# DenScript_5x5_Strip_Board.net
KiCad netlist of a schematic drawn in EAGLE
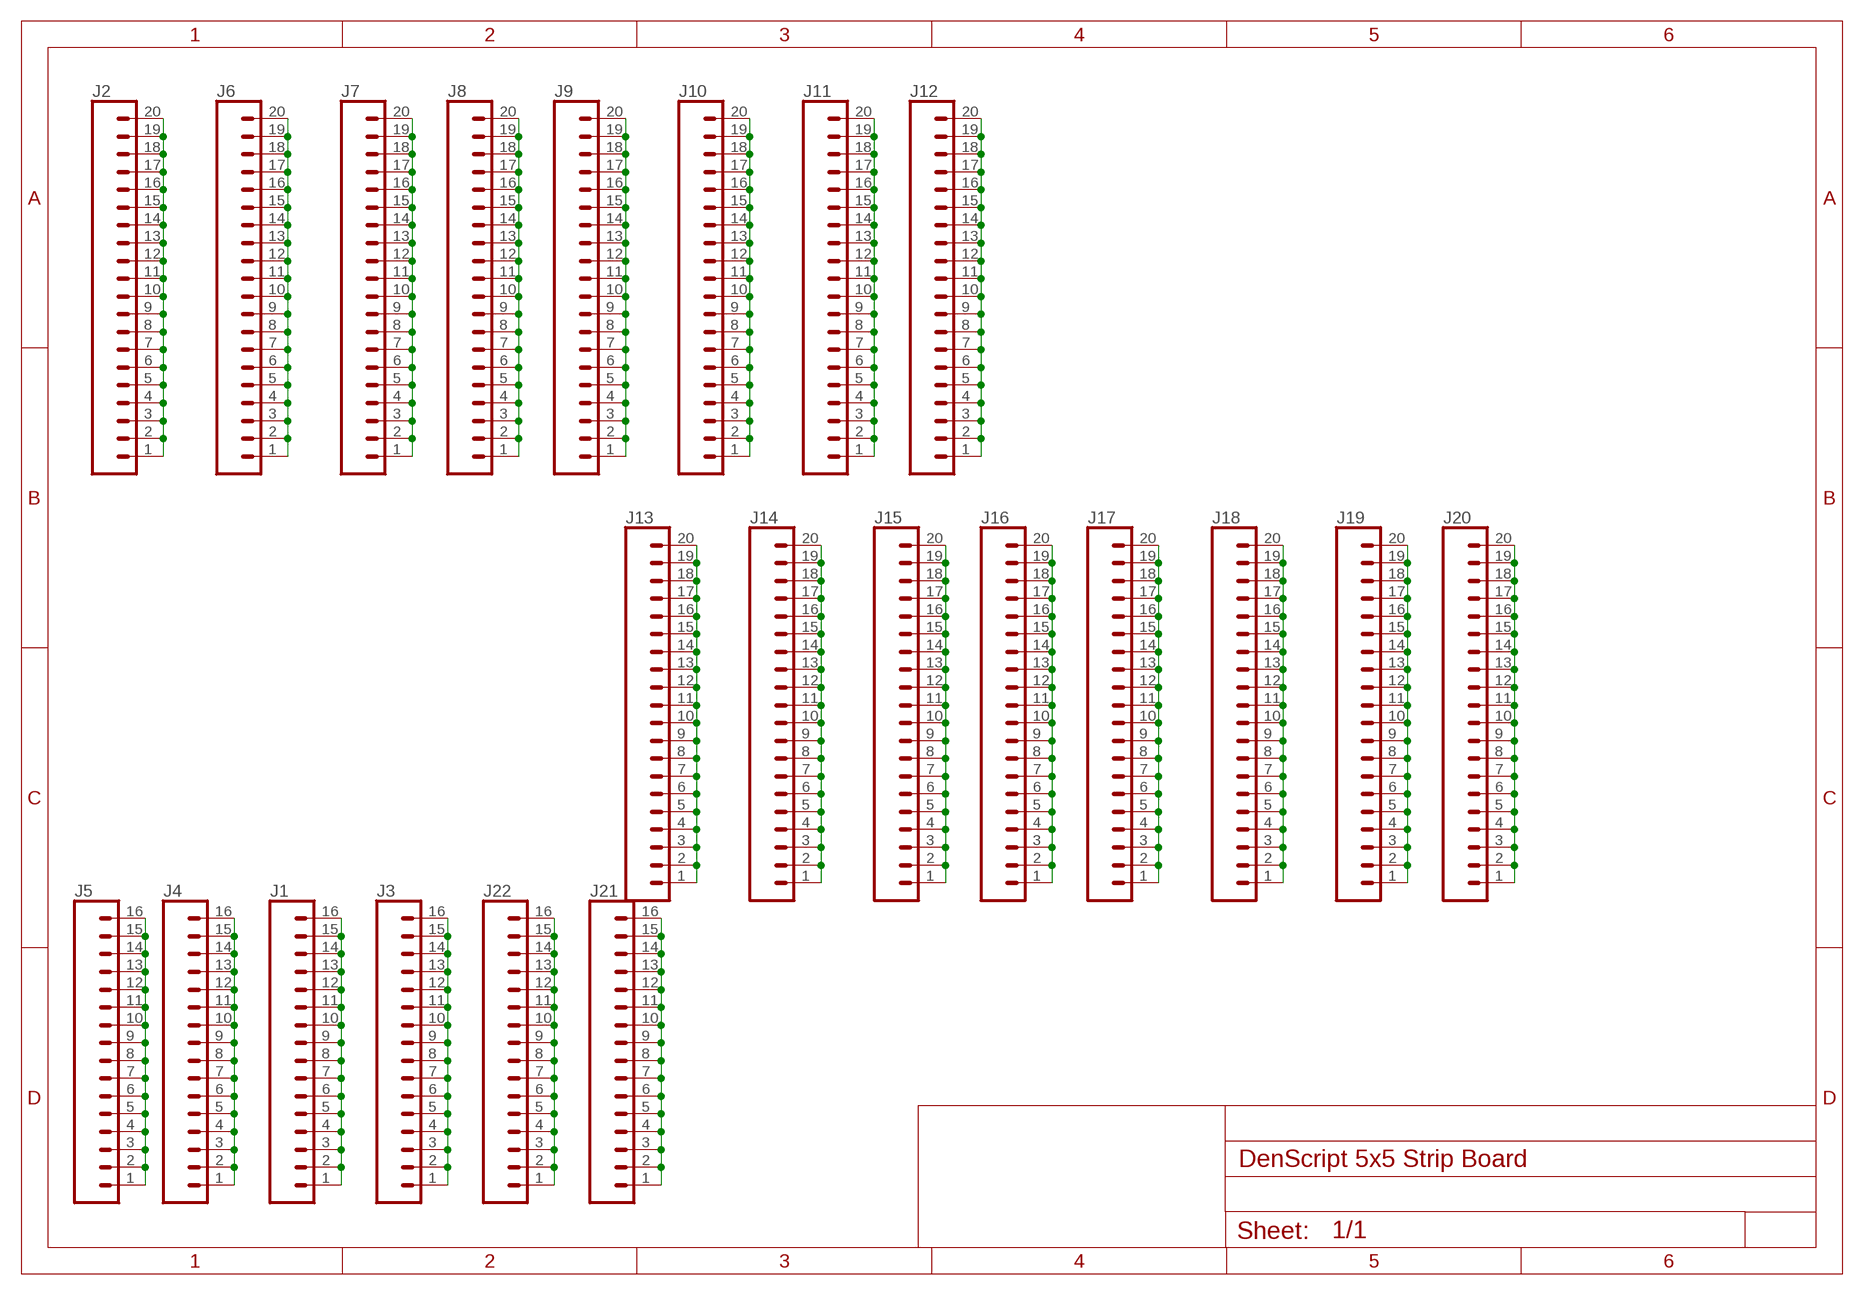
[diagram p0: schematic, sheet 1]

(export (version "E")
  (design (tool "Eeschema 10.0.6"))
  (components
    (comp (ref "J1")
      (value "CONN_161X16_NO_SILK")
      (footprint "eagle-import:1X16_NO_SILK")
      (libsource (lib "eagle-import") (part "CONN_161X16_NO_SILK"))
    )
    (comp (ref "J2")
      (value "CONN_20NOSILK")
      (footprint "eagle-import:1X20_NOSILK")
      (libsource (lib "eagle-import") (part "CONN_20NOSILK"))
    )
    (comp (ref "J3")
      (value "CONN_161X16_NO_SILK")
      (footprint "eagle-import:1X16_NO_SILK")
      (libsource (lib "eagle-import") (part "CONN_161X16_NO_SILK"))
    )
    (comp (ref "J4")
      (value "CONN_161X16_NO_SILK")
      (footprint "eagle-import:1X16_NO_SILK")
      (libsource (lib "eagle-import") (part "CONN_161X16_NO_SILK"))
    )
    (comp (ref "J5")
      (value "CONN_161X16_NO_SILK")
      (footprint "eagle-import:1X16_NO_SILK")
      (libsource (lib "eagle-import") (part "CONN_161X16_NO_SILK"))
    )
    (comp (ref "J6")
      (value "CONN_20NOSILK")
      (footprint "eagle-import:1X20_NOSILK")
      (libsource (lib "eagle-import") (part "CONN_20NOSILK"))
    )
    (comp (ref "J7")
      (value "CONN_20NOSILK")
      (footprint "eagle-import:1X20_NOSILK")
      (libsource (lib "eagle-import") (part "CONN_20NOSILK"))
    )
    (comp (ref "J8")
      (value "CONN_20NOSILK")
      (footprint "eagle-import:1X20_NOSILK")
      (libsource (lib "eagle-import") (part "CONN_20NOSILK"))
    )
    (comp (ref "J9")
      (value "CONN_20NOSILK")
      (footprint "eagle-import:1X20_NOSILK")
      (libsource (lib "eagle-import") (part "CONN_20NOSILK"))
    )
    (comp (ref "J10")
      (value "CONN_20NOSILK")
      (footprint "eagle-import:1X20_NOSILK")
      (libsource (lib "eagle-import") (part "CONN_20NOSILK"))
    )
    (comp (ref "J11")
      (value "CONN_20NOSILK")
      (footprint "eagle-import:1X20_NOSILK")
      (libsource (lib "eagle-import") (part "CONN_20NOSILK"))
    )
    (comp (ref "J12")
      (value "CONN_20NOSILK")
      (footprint "eagle-import:1X20_NOSILK")
      (libsource (lib "eagle-import") (part "CONN_20NOSILK"))
    )
    (comp (ref "J13")
      (value "CONN_20NOSILK")
      (footprint "eagle-import:1X20_NOSILK")
      (libsource (lib "eagle-import") (part "CONN_20NOSILK"))
    )
    (comp (ref "J14")
      (value "CONN_20NOSILK")
      (footprint "eagle-import:1X20_NOSILK")
      (libsource (lib "eagle-import") (part "CONN_20NOSILK"))
    )
    (comp (ref "J15")
      (value "CONN_20NOSILK")
      (footprint "eagle-import:1X20_NOSILK")
      (libsource (lib "eagle-import") (part "CONN_20NOSILK"))
    )
    (comp (ref "J16")
      (value "CONN_20NOSILK")
      (footprint "eagle-import:1X20_NOSILK")
      (libsource (lib "eagle-import") (part "CONN_20NOSILK"))
    )
    (comp (ref "J17")
      (value "CONN_20NOSILK")
      (footprint "eagle-import:1X20_NOSILK")
      (libsource (lib "eagle-import") (part "CONN_20NOSILK"))
    )
    (comp (ref "J18")
      (value "CONN_20NOSILK")
      (footprint "eagle-import:1X20_NOSILK")
      (libsource (lib "eagle-import") (part "CONN_20NOSILK"))
    )
    (comp (ref "J19")
      (value "CONN_20NOSILK")
      (footprint "eagle-import:1X20_NOSILK")
      (libsource (lib "eagle-import") (part "CONN_20NOSILK"))
    )
    (comp (ref "J20")
      (value "CONN_20NOSILK")
      (footprint "eagle-import:1X20_NOSILK")
      (libsource (lib "eagle-import") (part "CONN_20NOSILK"))
    )
    (comp (ref "J21")
      (value "CONN_161X16_NO_SILK")
      (footprint "eagle-import:1X16_NO_SILK")
      (libsource (lib "eagle-import") (part "CONN_161X16_NO_SILK"))
    )
    (comp (ref "J22")
      (value "CONN_161X16_NO_SILK")
      (footprint "eagle-import:1X16_NO_SILK")
      (libsource (lib "eagle-import") (part "CONN_161X16_NO_SILK"))
    )
  )
  (nets
    (net (code "1") (name "Net-(J1-Pad1)") (class "Default")
      (node (ref "J1") (pin "1") (pinfunction "1_1") (pintype "passive"))
      (node (ref "J1") (pin "10") (pinfunction "10_10") (pintype "passive"))
      (node (ref "J1") (pin "11") (pinfunction "11_11") (pintype "passive"))
      (node (ref "J1") (pin "12") (pinfunction "12_12") (pintype "passive"))
      (node (ref "J1") (pin "13") (pinfunction "13_13") (pintype "passive"))
      (node (ref "J1") (pin "14") (pinfunction "14_14") (pintype "passive"))
      (node (ref "J1") (pin "15") (pinfunction "15_15") (pintype "passive"))
      (node (ref "J1") (pin "16") (pinfunction "16_16") (pintype "passive"))
      (node (ref "J1") (pin "2") (pinfunction "2_2") (pintype "passive"))
      (node (ref "J1") (pin "3") (pinfunction "3_3") (pintype "passive"))
      (node (ref "J1") (pin "4") (pinfunction "4_4") (pintype "passive"))
      (node (ref "J1") (pin "5") (pinfunction "5_5") (pintype "passive"))
      (node (ref "J1") (pin "6") (pinfunction "6_6") (pintype "passive"))
      (node (ref "J1") (pin "7") (pinfunction "7_7") (pintype "passive"))
      (node (ref "J1") (pin "8") (pinfunction "8_8") (pintype "passive"))
      (node (ref "J1") (pin "9") (pinfunction "9_9") (pintype "passive"))
    )
    (net (code "2") (name "Net-(J2-Pad1)") (class "Default")
      (node (ref "J2") (pin "1") (pinfunction "1_1") (pintype "passive"))
      (node (ref "J2") (pin "10") (pinfunction "10_10") (pintype "passive"))
      (node (ref "J2") (pin "11") (pinfunction "11_11") (pintype "passive"))
      (node (ref "J2") (pin "12") (pinfunction "12_12") (pintype "passive"))
      (node (ref "J2") (pin "13") (pinfunction "13_13") (pintype "passive"))
      (node (ref "J2") (pin "14") (pinfunction "14_14") (pintype "passive"))
      (node (ref "J2") (pin "15") (pinfunction "15_15") (pintype "passive"))
      (node (ref "J2") (pin "16") (pinfunction "16_16") (pintype "passive"))
      (node (ref "J2") (pin "17") (pinfunction "17_17") (pintype "passive"))
      (node (ref "J2") (pin "18") (pinfunction "18_18") (pintype "passive"))
      (node (ref "J2") (pin "19") (pinfunction "19_19") (pintype "passive"))
      (node (ref "J2") (pin "2") (pinfunction "2_2") (pintype "passive"))
      (node (ref "J2") (pin "20") (pinfunction "20_20") (pintype "passive"))
      (node (ref "J2") (pin "3") (pinfunction "3_3") (pintype "passive"))
      (node (ref "J2") (pin "4") (pinfunction "4_4") (pintype "passive"))
      (node (ref "J2") (pin "5") (pinfunction "5_5") (pintype "passive"))
      (node (ref "J2") (pin "6") (pinfunction "6_6") (pintype "passive"))
      (node (ref "J2") (pin "7") (pinfunction "7_7") (pintype "passive"))
      (node (ref "J2") (pin "8") (pinfunction "8_8") (pintype "passive"))
      (node (ref "J2") (pin "9") (pinfunction "9_9") (pintype "passive"))
    )
    (net (code "3") (name "Net-(J3-Pad1)") (class "Default")
      (node (ref "J3") (pin "1") (pinfunction "1_1") (pintype "passive"))
      (node (ref "J3") (pin "10") (pinfunction "10_10") (pintype "passive"))
      (node (ref "J3") (pin "11") (pinfunction "11_11") (pintype "passive"))
      (node (ref "J3") (pin "12") (pinfunction "12_12") (pintype "passive"))
      (node (ref "J3") (pin "13") (pinfunction "13_13") (pintype "passive"))
      (node (ref "J3") (pin "14") (pinfunction "14_14") (pintype "passive"))
      (node (ref "J3") (pin "15") (pinfunction "15_15") (pintype "passive"))
      (node (ref "J3") (pin "16") (pinfunction "16_16") (pintype "passive"))
      (node (ref "J3") (pin "2") (pinfunction "2_2") (pintype "passive"))
      (node (ref "J3") (pin "3") (pinfunction "3_3") (pintype "passive"))
      (node (ref "J3") (pin "4") (pinfunction "4_4") (pintype "passive"))
      (node (ref "J3") (pin "5") (pinfunction "5_5") (pintype "passive"))
      (node (ref "J3") (pin "6") (pinfunction "6_6") (pintype "passive"))
      (node (ref "J3") (pin "7") (pinfunction "7_7") (pintype "passive"))
      (node (ref "J3") (pin "8") (pinfunction "8_8") (pintype "passive"))
      (node (ref "J3") (pin "9") (pinfunction "9_9") (pintype "passive"))
    )
    (net (code "4") (name "Net-(J4-Pad1)") (class "Default")
      (node (ref "J4") (pin "1") (pinfunction "1_1") (pintype "passive"))
      (node (ref "J4") (pin "10") (pinfunction "10_10") (pintype "passive"))
      (node (ref "J4") (pin "11") (pinfunction "11_11") (pintype "passive"))
      (node (ref "J4") (pin "12") (pinfunction "12_12") (pintype "passive"))
      (node (ref "J4") (pin "13") (pinfunction "13_13") (pintype "passive"))
      (node (ref "J4") (pin "14") (pinfunction "14_14") (pintype "passive"))
      (node (ref "J4") (pin "15") (pinfunction "15_15") (pintype "passive"))
      (node (ref "J4") (pin "16") (pinfunction "16_16") (pintype "passive"))
      (node (ref "J4") (pin "2") (pinfunction "2_2") (pintype "passive"))
      (node (ref "J4") (pin "3") (pinfunction "3_3") (pintype "passive"))
      (node (ref "J4") (pin "4") (pinfunction "4_4") (pintype "passive"))
      (node (ref "J4") (pin "5") (pinfunction "5_5") (pintype "passive"))
      (node (ref "J4") (pin "6") (pinfunction "6_6") (pintype "passive"))
      (node (ref "J4") (pin "7") (pinfunction "7_7") (pintype "passive"))
      (node (ref "J4") (pin "8") (pinfunction "8_8") (pintype "passive"))
      (node (ref "J4") (pin "9") (pinfunction "9_9") (pintype "passive"))
    )
    (net (code "5") (name "Net-(J5-Pad1)") (class "Default")
      (node (ref "J5") (pin "1") (pinfunction "1_1") (pintype "passive"))
      (node (ref "J5") (pin "10") (pinfunction "10_10") (pintype "passive"))
      (node (ref "J5") (pin "11") (pinfunction "11_11") (pintype "passive"))
      (node (ref "J5") (pin "12") (pinfunction "12_12") (pintype "passive"))
      (node (ref "J5") (pin "13") (pinfunction "13_13") (pintype "passive"))
      (node (ref "J5") (pin "14") (pinfunction "14_14") (pintype "passive"))
      (node (ref "J5") (pin "15") (pinfunction "15_15") (pintype "passive"))
      (node (ref "J5") (pin "16") (pinfunction "16_16") (pintype "passive"))
      (node (ref "J5") (pin "2") (pinfunction "2_2") (pintype "passive"))
      (node (ref "J5") (pin "3") (pinfunction "3_3") (pintype "passive"))
      (node (ref "J5") (pin "4") (pinfunction "4_4") (pintype "passive"))
      (node (ref "J5") (pin "5") (pinfunction "5_5") (pintype "passive"))
      (node (ref "J5") (pin "6") (pinfunction "6_6") (pintype "passive"))
      (node (ref "J5") (pin "7") (pinfunction "7_7") (pintype "passive"))
      (node (ref "J5") (pin "8") (pinfunction "8_8") (pintype "passive"))
      (node (ref "J5") (pin "9") (pinfunction "9_9") (pintype "passive"))
    )
    (net (code "6") (name "Net-(J6-Pad1)") (class "Default")
      (node (ref "J6") (pin "1") (pinfunction "1_1") (pintype "passive"))
      (node (ref "J6") (pin "10") (pinfunction "10_10") (pintype "passive"))
      (node (ref "J6") (pin "11") (pinfunction "11_11") (pintype "passive"))
      (node (ref "J6") (pin "12") (pinfunction "12_12") (pintype "passive"))
      (node (ref "J6") (pin "13") (pinfunction "13_13") (pintype "passive"))
      (node (ref "J6") (pin "14") (pinfunction "14_14") (pintype "passive"))
      (node (ref "J6") (pin "15") (pinfunction "15_15") (pintype "passive"))
      (node (ref "J6") (pin "16") (pinfunction "16_16") (pintype "passive"))
      (node (ref "J6") (pin "17") (pinfunction "17_17") (pintype "passive"))
      (node (ref "J6") (pin "18") (pinfunction "18_18") (pintype "passive"))
      (node (ref "J6") (pin "19") (pinfunction "19_19") (pintype "passive"))
      (node (ref "J6") (pin "2") (pinfunction "2_2") (pintype "passive"))
      (node (ref "J6") (pin "20") (pinfunction "20_20") (pintype "passive"))
      (node (ref "J6") (pin "3") (pinfunction "3_3") (pintype "passive"))
      (node (ref "J6") (pin "4") (pinfunction "4_4") (pintype "passive"))
      (node (ref "J6") (pin "5") (pinfunction "5_5") (pintype "passive"))
      (node (ref "J6") (pin "6") (pinfunction "6_6") (pintype "passive"))
      (node (ref "J6") (pin "7") (pinfunction "7_7") (pintype "passive"))
      (node (ref "J6") (pin "8") (pinfunction "8_8") (pintype "passive"))
      (node (ref "J6") (pin "9") (pinfunction "9_9") (pintype "passive"))
    )
    (net (code "7") (name "Net-(J7-Pad1)") (class "Default")
      (node (ref "J7") (pin "1") (pinfunction "1_1") (pintype "passive"))
      (node (ref "J7") (pin "10") (pinfunction "10_10") (pintype "passive"))
      (node (ref "J7") (pin "11") (pinfunction "11_11") (pintype "passive"))
      (node (ref "J7") (pin "12") (pinfunction "12_12") (pintype "passive"))
      (node (ref "J7") (pin "13") (pinfunction "13_13") (pintype "passive"))
      (node (ref "J7") (pin "14") (pinfunction "14_14") (pintype "passive"))
      (node (ref "J7") (pin "15") (pinfunction "15_15") (pintype "passive"))
      (node (ref "J7") (pin "16") (pinfunction "16_16") (pintype "passive"))
      (node (ref "J7") (pin "17") (pinfunction "17_17") (pintype "passive"))
      (node (ref "J7") (pin "18") (pinfunction "18_18") (pintype "passive"))
      (node (ref "J7") (pin "19") (pinfunction "19_19") (pintype "passive"))
      (node (ref "J7") (pin "2") (pinfunction "2_2") (pintype "passive"))
      (node (ref "J7") (pin "20") (pinfunction "20_20") (pintype "passive"))
      (node (ref "J7") (pin "3") (pinfunction "3_3") (pintype "passive"))
      (node (ref "J7") (pin "4") (pinfunction "4_4") (pintype "passive"))
      (node (ref "J7") (pin "5") (pinfunction "5_5") (pintype "passive"))
      (node (ref "J7") (pin "6") (pinfunction "6_6") (pintype "passive"))
      (node (ref "J7") (pin "7") (pinfunction "7_7") (pintype "passive"))
      (node (ref "J7") (pin "8") (pinfunction "8_8") (pintype "passive"))
      (node (ref "J7") (pin "9") (pinfunction "9_9") (pintype "passive"))
    )
    (net (code "8") (name "Net-(J8-Pad1)") (class "Default")
      (node (ref "J8") (pin "1") (pinfunction "1_1") (pintype "passive"))
      (node (ref "J8") (pin "10") (pinfunction "10_10") (pintype "passive"))
      (node (ref "J8") (pin "11") (pinfunction "11_11") (pintype "passive"))
      (node (ref "J8") (pin "12") (pinfunction "12_12") (pintype "passive"))
      (node (ref "J8") (pin "13") (pinfunction "13_13") (pintype "passive"))
      (node (ref "J8") (pin "14") (pinfunction "14_14") (pintype "passive"))
      (node (ref "J8") (pin "15") (pinfunction "15_15") (pintype "passive"))
      (node (ref "J8") (pin "16") (pinfunction "16_16") (pintype "passive"))
      (node (ref "J8") (pin "17") (pinfunction "17_17") (pintype "passive"))
      (node (ref "J8") (pin "18") (pinfunction "18_18") (pintype "passive"))
      (node (ref "J8") (pin "19") (pinfunction "19_19") (pintype "passive"))
      (node (ref "J8") (pin "2") (pinfunction "2_2") (pintype "passive"))
      (node (ref "J8") (pin "20") (pinfunction "20_20") (pintype "passive"))
      (node (ref "J8") (pin "3") (pinfunction "3_3") (pintype "passive"))
      (node (ref "J8") (pin "4") (pinfunction "4_4") (pintype "passive"))
      (node (ref "J8") (pin "5") (pinfunction "5_5") (pintype "passive"))
      (node (ref "J8") (pin "6") (pinfunction "6_6") (pintype "passive"))
      (node (ref "J8") (pin "7") (pinfunction "7_7") (pintype "passive"))
      (node (ref "J8") (pin "8") (pinfunction "8_8") (pintype "passive"))
      (node (ref "J8") (pin "9") (pinfunction "9_9") (pintype "passive"))
    )
    (net (code "9") (name "Net-(J9-Pad1)") (class "Default")
      (node (ref "J9") (pin "1") (pinfunction "1_1") (pintype "passive"))
      (node (ref "J9") (pin "10") (pinfunction "10_10") (pintype "passive"))
      (node (ref "J9") (pin "11") (pinfunction "11_11") (pintype "passive"))
      (node (ref "J9") (pin "12") (pinfunction "12_12") (pintype "passive"))
      (node (ref "J9") (pin "13") (pinfunction "13_13") (pintype "passive"))
      (node (ref "J9") (pin "14") (pinfunction "14_14") (pintype "passive"))
      (node (ref "J9") (pin "15") (pinfunction "15_15") (pintype "passive"))
      (node (ref "J9") (pin "16") (pinfunction "16_16") (pintype "passive"))
      (node (ref "J9") (pin "17") (pinfunction "17_17") (pintype "passive"))
      (node (ref "J9") (pin "18") (pinfunction "18_18") (pintype "passive"))
      (node (ref "J9") (pin "19") (pinfunction "19_19") (pintype "passive"))
      (node (ref "J9") (pin "2") (pinfunction "2_2") (pintype "passive"))
      (node (ref "J9") (pin "20") (pinfunction "20_20") (pintype "passive"))
      (node (ref "J9") (pin "3") (pinfunction "3_3") (pintype "passive"))
      (node (ref "J9") (pin "4") (pinfunction "4_4") (pintype "passive"))
      (node (ref "J9") (pin "5") (pinfunction "5_5") (pintype "passive"))
      (node (ref "J9") (pin "6") (pinfunction "6_6") (pintype "passive"))
      (node (ref "J9") (pin "7") (pinfunction "7_7") (pintype "passive"))
      (node (ref "J9") (pin "8") (pinfunction "8_8") (pintype "passive"))
      (node (ref "J9") (pin "9") (pinfunction "9_9") (pintype "passive"))
    )
    (net (code "10") (name "Net-(J10-Pad1)") (class "Default")
      (node (ref "J10") (pin "1") (pinfunction "1_1") (pintype "passive"))
      (node (ref "J10") (pin "10") (pinfunction "10_10") (pintype "passive"))
      (node (ref "J10") (pin "11") (pinfunction "11_11") (pintype "passive"))
      (node (ref "J10") (pin "12") (pinfunction "12_12") (pintype "passive"))
      (node (ref "J10") (pin "13") (pinfunction "13_13") (pintype "passive"))
      (node (ref "J10") (pin "14") (pinfunction "14_14") (pintype "passive"))
      (node (ref "J10") (pin "15") (pinfunction "15_15") (pintype "passive"))
      (node (ref "J10") (pin "16") (pinfunction "16_16") (pintype "passive"))
      (node (ref "J10") (pin "17") (pinfunction "17_17") (pintype "passive"))
      (node (ref "J10") (pin "18") (pinfunction "18_18") (pintype "passive"))
      (node (ref "J10") (pin "19") (pinfunction "19_19") (pintype "passive"))
      (node (ref "J10") (pin "2") (pinfunction "2_2") (pintype "passive"))
      (node (ref "J10") (pin "20") (pinfunction "20_20") (pintype "passive"))
      (node (ref "J10") (pin "3") (pinfunction "3_3") (pintype "passive"))
      (node (ref "J10") (pin "4") (pinfunction "4_4") (pintype "passive"))
      (node (ref "J10") (pin "5") (pinfunction "5_5") (pintype "passive"))
      (node (ref "J10") (pin "6") (pinfunction "6_6") (pintype "passive"))
      (node (ref "J10") (pin "7") (pinfunction "7_7") (pintype "passive"))
      (node (ref "J10") (pin "8") (pinfunction "8_8") (pintype "passive"))
      (node (ref "J10") (pin "9") (pinfunction "9_9") (pintype "passive"))
    )
    (net (code "11") (name "Net-(J11-Pad1)") (class "Default")
      (node (ref "J11") (pin "1") (pinfunction "1_1") (pintype "passive"))
      (node (ref "J11") (pin "10") (pinfunction "10_10") (pintype "passive"))
      (node (ref "J11") (pin "11") (pinfunction "11_11") (pintype "passive"))
      (node (ref "J11") (pin "12") (pinfunction "12_12") (pintype "passive"))
      (node (ref "J11") (pin "13") (pinfunction "13_13") (pintype "passive"))
      (node (ref "J11") (pin "14") (pinfunction "14_14") (pintype "passive"))
      (node (ref "J11") (pin "15") (pinfunction "15_15") (pintype "passive"))
      (node (ref "J11") (pin "16") (pinfunction "16_16") (pintype "passive"))
      (node (ref "J11") (pin "17") (pinfunction "17_17") (pintype "passive"))
      (node (ref "J11") (pin "18") (pinfunction "18_18") (pintype "passive"))
      (node (ref "J11") (pin "19") (pinfunction "19_19") (pintype "passive"))
      (node (ref "J11") (pin "2") (pinfunction "2_2") (pintype "passive"))
      (node (ref "J11") (pin "20") (pinfunction "20_20") (pintype "passive"))
      (node (ref "J11") (pin "3") (pinfunction "3_3") (pintype "passive"))
      (node (ref "J11") (pin "4") (pinfunction "4_4") (pintype "passive"))
      (node (ref "J11") (pin "5") (pinfunction "5_5") (pintype "passive"))
      (node (ref "J11") (pin "6") (pinfunction "6_6") (pintype "passive"))
      (node (ref "J11") (pin "7") (pinfunction "7_7") (pintype "passive"))
      (node (ref "J11") (pin "8") (pinfunction "8_8") (pintype "passive"))
      (node (ref "J11") (pin "9") (pinfunction "9_9") (pintype "passive"))
    )
    (net (code "12") (name "Net-(J12-Pad1)") (class "Default")
      (node (ref "J12") (pin "1") (pinfunction "1_1") (pintype "passive"))
      (node (ref "J12") (pin "10") (pinfunction "10_10") (pintype "passive"))
      (node (ref "J12") (pin "11") (pinfunction "11_11") (pintype "passive"))
      (node (ref "J12") (pin "12") (pinfunction "12_12") (pintype "passive"))
      (node (ref "J12") (pin "13") (pinfunction "13_13") (pintype "passive"))
      (node (ref "J12") (pin "14") (pinfunction "14_14") (pintype "passive"))
      (node (ref "J12") (pin "15") (pinfunction "15_15") (pintype "passive"))
      (node (ref "J12") (pin "16") (pinfunction "16_16") (pintype "passive"))
      (node (ref "J12") (pin "17") (pinfunction "17_17") (pintype "passive"))
      (node (ref "J12") (pin "18") (pinfunction "18_18") (pintype "passive"))
      (node (ref "J12") (pin "19") (pinfunction "19_19") (pintype "passive"))
      (node (ref "J12") (pin "2") (pinfunction "2_2") (pintype "passive"))
      (node (ref "J12") (pin "20") (pinfunction "20_20") (pintype "passive"))
      (node (ref "J12") (pin "3") (pinfunction "3_3") (pintype "passive"))
      (node (ref "J12") (pin "4") (pinfunction "4_4") (pintype "passive"))
      (node (ref "J12") (pin "5") (pinfunction "5_5") (pintype "passive"))
      (node (ref "J12") (pin "6") (pinfunction "6_6") (pintype "passive"))
      (node (ref "J12") (pin "7") (pinfunction "7_7") (pintype "passive"))
      (node (ref "J12") (pin "8") (pinfunction "8_8") (pintype "passive"))
      (node (ref "J12") (pin "9") (pinfunction "9_9") (pintype "passive"))
    )
    (net (code "13") (name "Net-(J13-Pad1)") (class "Default")
      (node (ref "J13") (pin "1") (pinfunction "1_1") (pintype "passive"))
      (node (ref "J13") (pin "10") (pinfunction "10_10") (pintype "passive"))
      (node (ref "J13") (pin "11") (pinfunction "11_11") (pintype "passive"))
      (node (ref "J13") (pin "12") (pinfunction "12_12") (pintype "passive"))
      (node (ref "J13") (pin "13") (pinfunction "13_13") (pintype "passive"))
      (node (ref "J13") (pin "14") (pinfunction "14_14") (pintype "passive"))
      (node (ref "J13") (pin "15") (pinfunction "15_15") (pintype "passive"))
      (node (ref "J13") (pin "16") (pinfunction "16_16") (pintype "passive"))
      (node (ref "J13") (pin "17") (pinfunction "17_17") (pintype "passive"))
      (node (ref "J13") (pin "18") (pinfunction "18_18") (pintype "passive"))
      (node (ref "J13") (pin "19") (pinfunction "19_19") (pintype "passive"))
      (node (ref "J13") (pin "2") (pinfunction "2_2") (pintype "passive"))
      (node (ref "J13") (pin "20") (pinfunction "20_20") (pintype "passive"))
      (node (ref "J13") (pin "3") (pinfunction "3_3") (pintype "passive"))
      (node (ref "J13") (pin "4") (pinfunction "4_4") (pintype "passive"))
      (node (ref "J13") (pin "5") (pinfunction "5_5") (pintype "passive"))
      (node (ref "J13") (pin "6") (pinfunction "6_6") (pintype "passive"))
      (node (ref "J13") (pin "7") (pinfunction "7_7") (pintype "passive"))
      (node (ref "J13") (pin "8") (pinfunction "8_8") (pintype "passive"))
      (node (ref "J13") (pin "9") (pinfunction "9_9") (pintype "passive"))
    )
    (net (code "14") (name "Net-(J14-Pad1)") (class "Default")
      (node (ref "J14") (pin "1") (pinfunction "1_1") (pintype "passive"))
      (node (ref "J14") (pin "10") (pinfunction "10_10") (pintype "passive"))
      (node (ref "J14") (pin "11") (pinfunction "11_11") (pintype "passive"))
      (node (ref "J14") (pin "12") (pinfunction "12_12") (pintype "passive"))
      (node (ref "J14") (pin "13") (pinfunction "13_13") (pintype "passive"))
      (node (ref "J14") (pin "14") (pinfunction "14_14") (pintype "passive"))
      (node (ref "J14") (pin "15") (pinfunction "15_15") (pintype "passive"))
      (node (ref "J14") (pin "16") (pinfunction "16_16") (pintype "passive"))
      (node (ref "J14") (pin "17") (pinfunction "17_17") (pintype "passive"))
      (node (ref "J14") (pin "18") (pinfunction "18_18") (pintype "passive"))
      (node (ref "J14") (pin "19") (pinfunction "19_19") (pintype "passive"))
      (node (ref "J14") (pin "2") (pinfunction "2_2") (pintype "passive"))
      (node (ref "J14") (pin "20") (pinfunction "20_20") (pintype "passive"))
      (node (ref "J14") (pin "3") (pinfunction "3_3") (pintype "passive"))
      (node (ref "J14") (pin "4") (pinfunction "4_4") (pintype "passive"))
      (node (ref "J14") (pin "5") (pinfunction "5_5") (pintype "passive"))
      (node (ref "J14") (pin "6") (pinfunction "6_6") (pintype "passive"))
      (node (ref "J14") (pin "7") (pinfunction "7_7") (pintype "passive"))
      (node (ref "J14") (pin "8") (pinfunction "8_8") (pintype "passive"))
      (node (ref "J14") (pin "9") (pinfunction "9_9") (pintype "passive"))
    )
    (net (code "15") (name "Net-(J15-Pad1)") (class "Default")
      (node (ref "J15") (pin "1") (pinfunction "1_1") (pintype "passive"))
      (node (ref "J15") (pin "10") (pinfunction "10_10") (pintype "passive"))
      (node (ref "J15") (pin "11") (pinfunction "11_11") (pintype "passive"))
      (node (ref "J15") (pin "12") (pinfunction "12_12") (pintype "passive"))
      (node (ref "J15") (pin "13") (pinfunction "13_13") (pintype "passive"))
      (node (ref "J15") (pin "14") (pinfunction "14_14") (pintype "passive"))
      (node (ref "J15") (pin "15") (pinfunction "15_15") (pintype "passive"))
      (node (ref "J15") (pin "16") (pinfunction "16_16") (pintype "passive"))
      (node (ref "J15") (pin "17") (pinfunction "17_17") (pintype "passive"))
      (node (ref "J15") (pin "18") (pinfunction "18_18") (pintype "passive"))
      (node (ref "J15") (pin "19") (pinfunction "19_19") (pintype "passive"))
      (node (ref "J15") (pin "2") (pinfunction "2_2") (pintype "passive"))
      (node (ref "J15") (pin "20") (pinfunction "20_20") (pintype "passive"))
      (node (ref "J15") (pin "3") (pinfunction "3_3") (pintype "passive"))
      (node (ref "J15") (pin "4") (pinfunction "4_4") (pintype "passive"))
      (node (ref "J15") (pin "5") (pinfunction "5_5") (pintype "passive"))
      (node (ref "J15") (pin "6") (pinfunction "6_6") (pintype "passive"))
      (node (ref "J15") (pin "7") (pinfunction "7_7") (pintype "passive"))
      (node (ref "J15") (pin "8") (pinfunction "8_8") (pintype "passive"))
      (node (ref "J15") (pin "9") (pinfunction "9_9") (pintype "passive"))
    )
    (net (code "16") (name "Net-(J16-Pad1)") (class "Default")
      (node (ref "J16") (pin "1") (pinfunction "1_1") (pintype "passive"))
      (node (ref "J16") (pin "10") (pinfunction "10_10") (pintype "passive"))
      (node (ref "J16") (pin "11") (pinfunction "11_11") (pintype "passive"))
      (node (ref "J16") (pin "12") (pinfunction "12_12") (pintype "passive"))
      (node (ref "J16") (pin "13") (pinfunction "13_13") (pintype "passive"))
      (node (ref "J16") (pin "14") (pinfunction "14_14") (pintype "passive"))
      (node (ref "J16") (pin "15") (pinfunction "15_15") (pintype "passive"))
      (node (ref "J16") (pin "16") (pinfunction "16_16") (pintype "passive"))
      (node (ref "J16") (pin "17") (pinfunction "17_17") (pintype "passive"))
      (node (ref "J16") (pin "18") (pinfunction "18_18") (pintype "passive"))
      (node (ref "J16") (pin "19") (pinfunction "19_19") (pintype "passive"))
      (node (ref "J16") (pin "2") (pinfunction "2_2") (pintype "passive"))
      (node (ref "J16") (pin "20") (pinfunction "20_20") (pintype "passive"))
      (node (ref "J16") (pin "3") (pinfunction "3_3") (pintype "passive"))
      (node (ref "J16") (pin "4") (pinfunction "4_4") (pintype "passive"))
      (node (ref "J16") (pin "5") (pinfunction "5_5") (pintype "passive"))
      (node (ref "J16") (pin "6") (pinfunction "6_6") (pintype "passive"))
      (node (ref "J16") (pin "7") (pinfunction "7_7") (pintype "passive"))
      (node (ref "J16") (pin "8") (pinfunction "8_8") (pintype "passive"))
      (node (ref "J16") (pin "9") (pinfunction "9_9") (pintype "passive"))
    )
    (net (code "17") (name "Net-(J17-Pad1)") (class "Default")
      (node (ref "J17") (pin "1") (pinfunction "1_1") (pintype "passive"))
      (node (ref "J17") (pin "10") (pinfunction "10_10") (pintype "passive"))
      (node (ref "J17") (pin "11") (pinfunction "11_11") (pintype "passive"))
      (node (ref "J17") (pin "12") (pinfunction "12_12") (pintype "passive"))
      (node (ref "J17") (pin "13") (pinfunction "13_13") (pintype "passive"))
      (node (ref "J17") (pin "14") (pinfunction "14_14") (pintype "passive"))
      (node (ref "J17") (pin "15") (pinfunction "15_15") (pintype "passive"))
      (node (ref "J17") (pin "16") (pinfunction "16_16") (pintype "passive"))
      (node (ref "J17") (pin "17") (pinfunction "17_17") (pintype "passive"))
      (node (ref "J17") (pin "18") (pinfunction "18_18") (pintype "passive"))
      (node (ref "J17") (pin "19") (pinfunction "19_19") (pintype "passive"))
      (node (ref "J17") (pin "2") (pinfunction "2_2") (pintype "passive"))
      (node (ref "J17") (pin "20") (pinfunction "20_20") (pintype "passive"))
      (node (ref "J17") (pin "3") (pinfunction "3_3") (pintype "passive"))
      (node (ref "J17") (pin "4") (pinfunction "4_4") (pintype "passive"))
      (node (ref "J17") (pin "5") (pinfunction "5_5") (pintype "passive"))
      (node (ref "J17") (pin "6") (pinfunction "6_6") (pintype "passive"))
      (node (ref "J17") (pin "7") (pinfunction "7_7") (pintype "passive"))
      (node (ref "J17") (pin "8") (pinfunction "8_8") (pintype "passive"))
      (node (ref "J17") (pin "9") (pinfunction "9_9") (pintype "passive"))
    )
    (net (code "18") (name "Net-(J18-Pad1)") (class "Default")
      (node (ref "J18") (pin "1") (pinfunction "1_1") (pintype "passive"))
      (node (ref "J18") (pin "10") (pinfunction "10_10") (pintype "passive"))
      (node (ref "J18") (pin "11") (pinfunction "11_11") (pintype "passive"))
      (node (ref "J18") (pin "12") (pinfunction "12_12") (pintype "passive"))
      (node (ref "J18") (pin "13") (pinfunction "13_13") (pintype "passive"))
      (node (ref "J18") (pin "14") (pinfunction "14_14") (pintype "passive"))
      (node (ref "J18") (pin "15") (pinfunction "15_15") (pintype "passive"))
      (node (ref "J18") (pin "16") (pinfunction "16_16") (pintype "passive"))
      (node (ref "J18") (pin "17") (pinfunction "17_17") (pintype "passive"))
      (node (ref "J18") (pin "18") (pinfunction "18_18") (pintype "passive"))
      (node (ref "J18") (pin "19") (pinfunction "19_19") (pintype "passive"))
      (node (ref "J18") (pin "2") (pinfunction "2_2") (pintype "passive"))
      (node (ref "J18") (pin "20") (pinfunction "20_20") (pintype "passive"))
      (node (ref "J18") (pin "3") (pinfunction "3_3") (pintype "passive"))
      (node (ref "J18") (pin "4") (pinfunction "4_4") (pintype "passive"))
      (node (ref "J18") (pin "5") (pinfunction "5_5") (pintype "passive"))
      (node (ref "J18") (pin "6") (pinfunction "6_6") (pintype "passive"))
      (node (ref "J18") (pin "7") (pinfunction "7_7") (pintype "passive"))
      (node (ref "J18") (pin "8") (pinfunction "8_8") (pintype "passive"))
      (node (ref "J18") (pin "9") (pinfunction "9_9") (pintype "passive"))
    )
    (net (code "19") (name "Net-(J19-Pad1)") (class "Default")
      (node (ref "J19") (pin "1") (pinfunction "1_1") (pintype "passive"))
      (node (ref "J19") (pin "10") (pinfunction "10_10") (pintype "passive"))
      (node (ref "J19") (pin "11") (pinfunction "11_11") (pintype "passive"))
      (node (ref "J19") (pin "12") (pinfunction "12_12") (pintype "passive"))
      (node (ref "J19") (pin "13") (pinfunction "13_13") (pintype "passive"))
      (node (ref "J19") (pin "14") (pinfunction "14_14") (pintype "passive"))
      (node (ref "J19") (pin "15") (pinfunction "15_15") (pintype "passive"))
      (node (ref "J19") (pin "16") (pinfunction "16_16") (pintype "passive"))
      (node (ref "J19") (pin "17") (pinfunction "17_17") (pintype "passive"))
      (node (ref "J19") (pin "18") (pinfunction "18_18") (pintype "passive"))
      (node (ref "J19") (pin "19") (pinfunction "19_19") (pintype "passive"))
      (node (ref "J19") (pin "2") (pinfunction "2_2") (pintype "passive"))
      (node (ref "J19") (pin "20") (pinfunction "20_20") (pintype "passive"))
      (node (ref "J19") (pin "3") (pinfunction "3_3") (pintype "passive"))
      (node (ref "J19") (pin "4") (pinfunction "4_4") (pintype "passive"))
      (node (ref "J19") (pin "5") (pinfunction "5_5") (pintype "passive"))
      (node (ref "J19") (pin "6") (pinfunction "6_6") (pintype "passive"))
      (node (ref "J19") (pin "7") (pinfunction "7_7") (pintype "passive"))
      (node (ref "J19") (pin "8") (pinfunction "8_8") (pintype "passive"))
      (node (ref "J19") (pin "9") (pinfunction "9_9") (pintype "passive"))
    )
    (net (code "20") (name "Net-(J20-Pad1)") (class "Default")
      (node (ref "J20") (pin "1") (pinfunction "1_1") (pintype "passive"))
      (node (ref "J20") (pin "10") (pinfunction "10_10") (pintype "passive"))
      (node (ref "J20") (pin "11") (pinfunction "11_11") (pintype "passive"))
      (node (ref "J20") (pin "12") (pinfunction "12_12") (pintype "passive"))
      (node (ref "J20") (pin "13") (pinfunction "13_13") (pintype "passive"))
      (node (ref "J20") (pin "14") (pinfunction "14_14") (pintype "passive"))
      (node (ref "J20") (pin "15") (pinfunction "15_15") (pintype "passive"))
      (node (ref "J20") (pin "16") (pinfunction "16_16") (pintype "passive"))
      (node (ref "J20") (pin "17") (pinfunction "17_17") (pintype "passive"))
      (node (ref "J20") (pin "18") (pinfunction "18_18") (pintype "passive"))
      (node (ref "J20") (pin "19") (pinfunction "19_19") (pintype "passive"))
      (node (ref "J20") (pin "2") (pinfunction "2_2") (pintype "passive"))
      (node (ref "J20") (pin "20") (pinfunction "20_20") (pintype "passive"))
      (node (ref "J20") (pin "3") (pinfunction "3_3") (pintype "passive"))
      (node (ref "J20") (pin "4") (pinfunction "4_4") (pintype "passive"))
      (node (ref "J20") (pin "5") (pinfunction "5_5") (pintype "passive"))
      (node (ref "J20") (pin "6") (pinfunction "6_6") (pintype "passive"))
      (node (ref "J20") (pin "7") (pinfunction "7_7") (pintype "passive"))
      (node (ref "J20") (pin "8") (pinfunction "8_8") (pintype "passive"))
      (node (ref "J20") (pin "9") (pinfunction "9_9") (pintype "passive"))
    )
    (net (code "21") (name "Net-(J21-Pad1)") (class "Default")
      (node (ref "J21") (pin "1") (pinfunction "1_1") (pintype "passive"))
      (node (ref "J21") (pin "10") (pinfunction "10_10") (pintype "passive"))
      (node (ref "J21") (pin "11") (pinfunction "11_11") (pintype "passive"))
      (node (ref "J21") (pin "12") (pinfunction "12_12") (pintype "passive"))
      (node (ref "J21") (pin "13") (pinfunction "13_13") (pintype "passive"))
      (node (ref "J21") (pin "14") (pinfunction "14_14") (pintype "passive"))
      (node (ref "J21") (pin "15") (pinfunction "15_15") (pintype "passive"))
      (node (ref "J21") (pin "16") (pinfunction "16_16") (pintype "passive"))
      (node (ref "J21") (pin "2") (pinfunction "2_2") (pintype "passive"))
      (node (ref "J21") (pin "3") (pinfunction "3_3") (pintype "passive"))
      (node (ref "J21") (pin "4") (pinfunction "4_4") (pintype "passive"))
      (node (ref "J21") (pin "5") (pinfunction "5_5") (pintype "passive"))
      (node (ref "J21") (pin "6") (pinfunction "6_6") (pintype "passive"))
      (node (ref "J21") (pin "7") (pinfunction "7_7") (pintype "passive"))
      (node (ref "J21") (pin "8") (pinfunction "8_8") (pintype "passive"))
      (node (ref "J21") (pin "9") (pinfunction "9_9") (pintype "passive"))
    )
    (net (code "22") (name "Net-(J22-Pad1)") (class "Default")
      (node (ref "J22") (pin "1") (pinfunction "1_1") (pintype "passive"))
      (node (ref "J22") (pin "10") (pinfunction "10_10") (pintype "passive"))
      (node (ref "J22") (pin "11") (pinfunction "11_11") (pintype "passive"))
      (node (ref "J22") (pin "12") (pinfunction "12_12") (pintype "passive"))
      (node (ref "J22") (pin "13") (pinfunction "13_13") (pintype "passive"))
      (node (ref "J22") (pin "14") (pinfunction "14_14") (pintype "passive"))
      (node (ref "J22") (pin "15") (pinfunction "15_15") (pintype "passive"))
      (node (ref "J22") (pin "16") (pinfunction "16_16") (pintype "passive"))
      (node (ref "J22") (pin "2") (pinfunction "2_2") (pintype "passive"))
      (node (ref "J22") (pin "3") (pinfunction "3_3") (pintype "passive"))
      (node (ref "J22") (pin "4") (pinfunction "4_4") (pintype "passive"))
      (node (ref "J22") (pin "5") (pinfunction "5_5") (pintype "passive"))
      (node (ref "J22") (pin "6") (pinfunction "6_6") (pintype "passive"))
      (node (ref "J22") (pin "7") (pinfunction "7_7") (pintype "passive"))
      (node (ref "J22") (pin "8") (pinfunction "8_8") (pintype "passive"))
      (node (ref "J22") (pin "9") (pinfunction "9_9") (pintype "passive"))
    )
  )
)
